# Clock_WR.net
KiCad netlist of a schematic drawn in Altium Designer
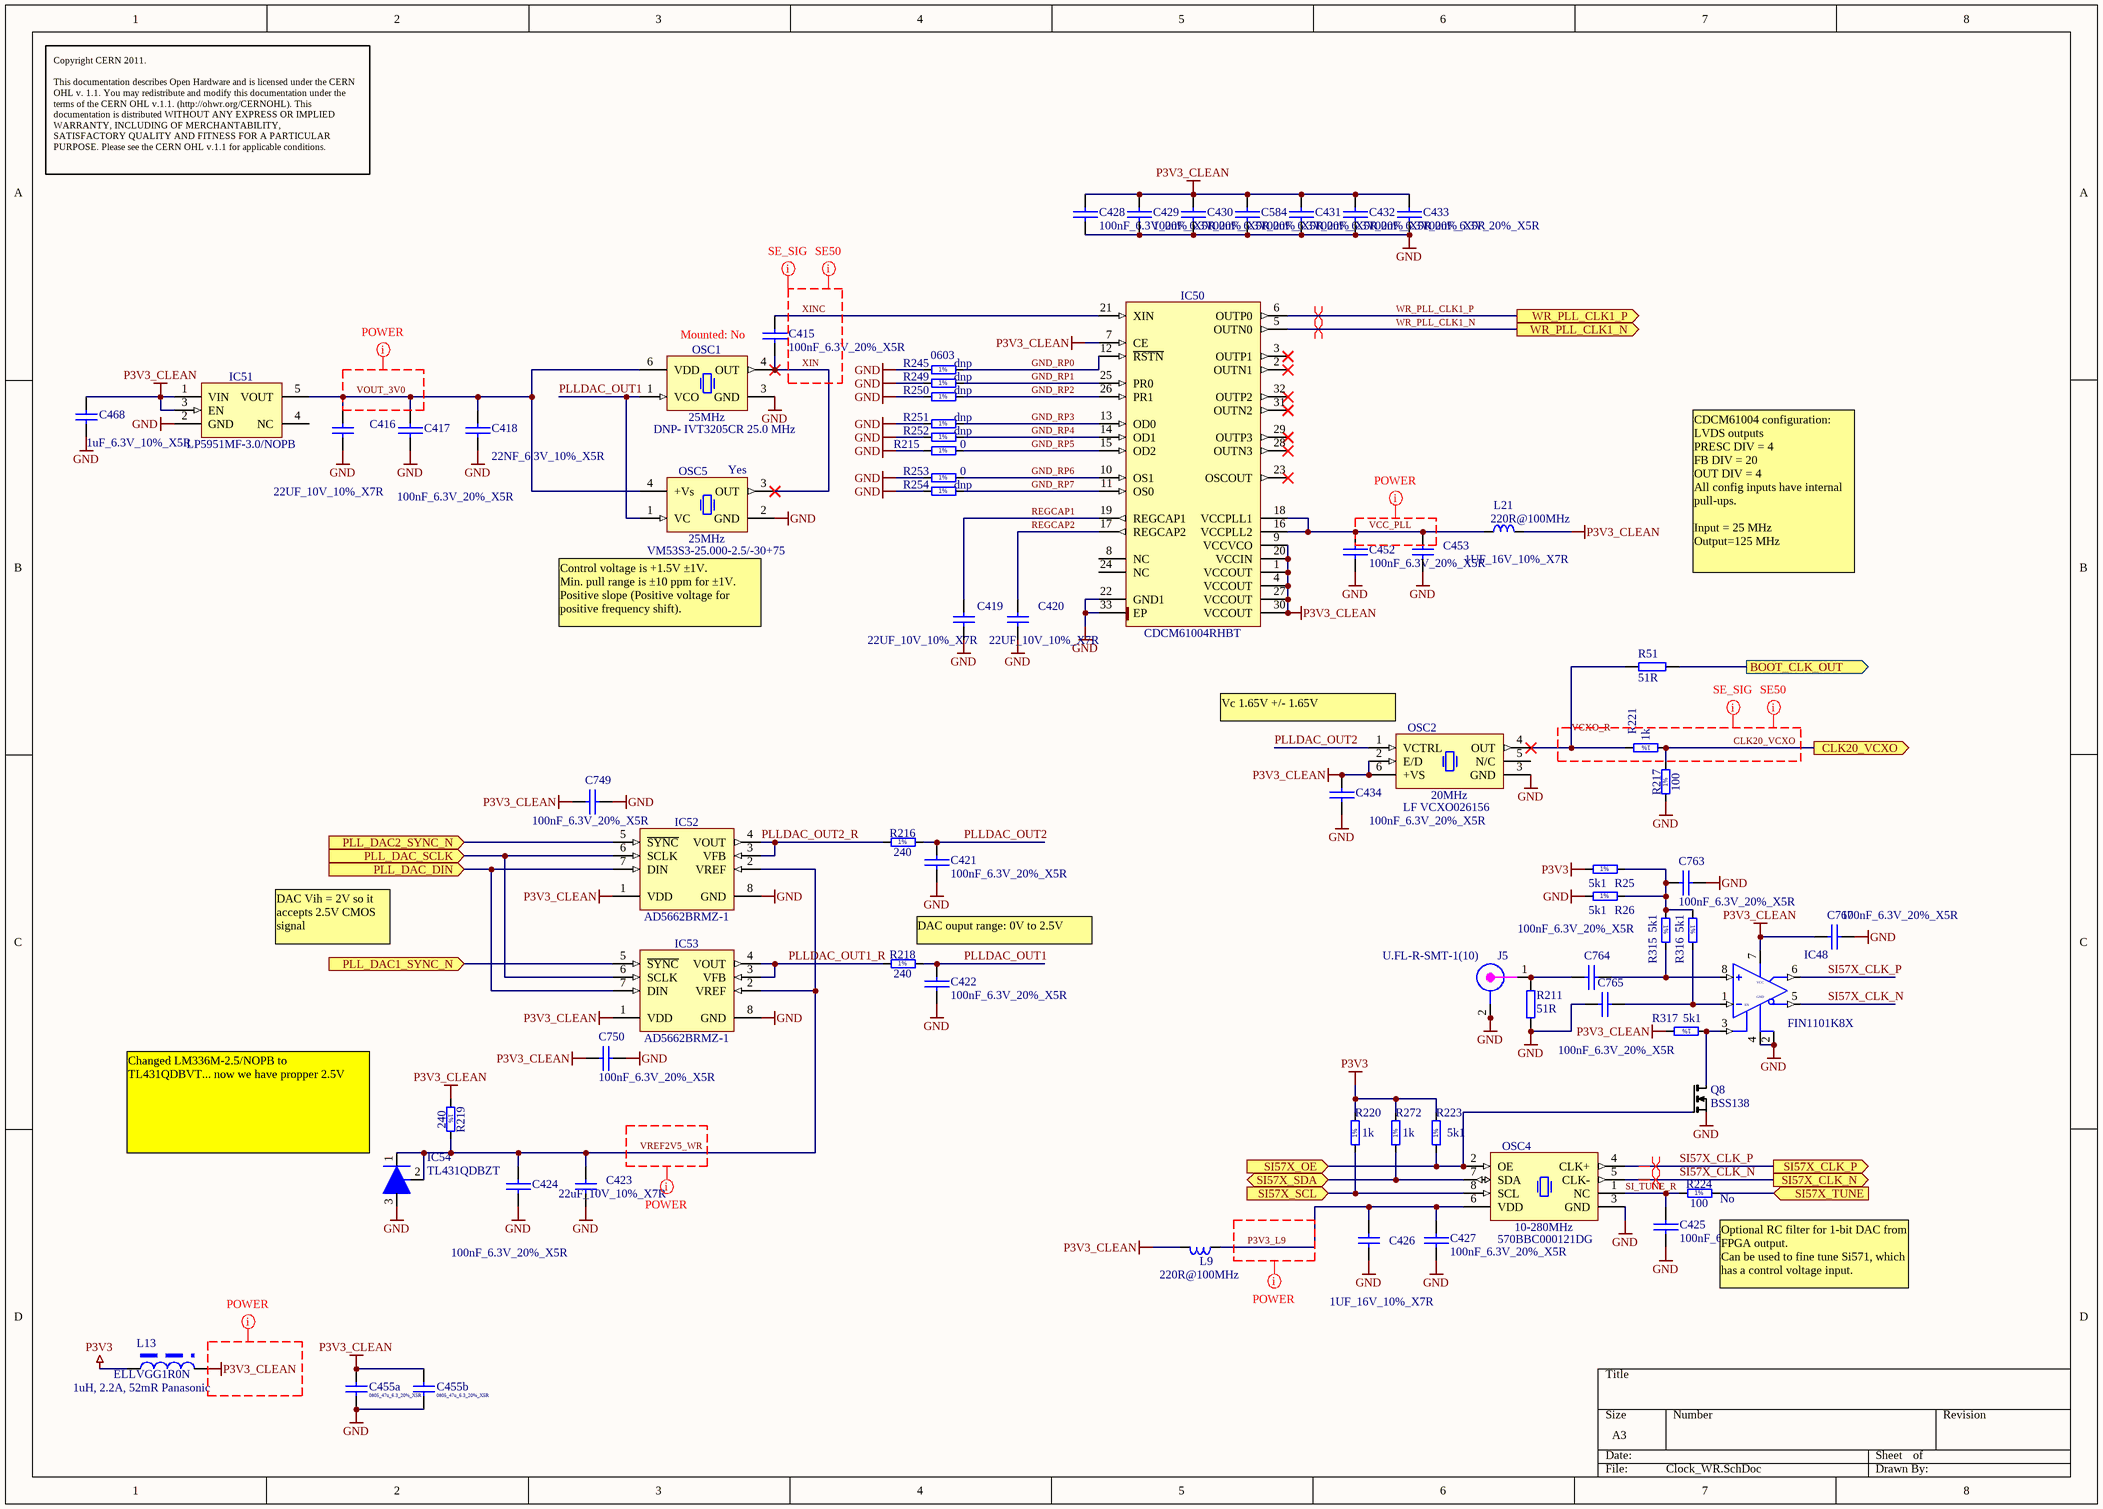
[diagram p0: Clock_WR.SchDoc]

(export (version "E")
  (design (tool "Eeschema 10.0.6"))
  (components
    (comp (ref "C415")
      (value "100nF_6.3V_20%_X5R")
      (footprint "0201C")
      (description "Capacitor SMD")
      (libsource (lib "LIBRARY_SCH") (part "CAP_SMD_0201"))
    )
    (comp (ref "C416")
      (value "22UF_10V_10%_X7R")
      (footprint "CAPC1608X87N")
      (description "Non-polarised capacitor")
      (fields
        (field (name "PART NUMBER") "CC0603_1UF_16V_10%_X7R")
        (field (name "VOLTAGE") "16V")
        (field (name "AUTHOR") "CERN DEM JLC")
      )
      (libsource (lib "Capacitors") (part "Capacitor - non polarized"))
    )
    (comp (ref "C417")
      (value "100nF_6.3V_20%_X5R")
      (footprint "0201C")
      (description "Capacitor SMD")
      (libsource (lib "LIBRARY_SCH") (part "CAP_SMD_0201"))
    )
    (comp (ref "C418")
      (value "22NF_6.3V_10%_X5R")
      (footprint "0201C")
      (description "Capacitor SMD")
      (libsource (lib "LIBRARY_SCH") (part "CAP_SMD_0201"))
    )
    (comp (ref "C419")
      (value "22UF_10V_10%_X7R")
      (footprint "CAPC3216X180N")
      (description "Non-polarised capacitor")
      (fields
        (field (name "PART NUMBER") "CC1206_22UF_10V_10%_X7R")
        (field (name "VOLTAGE") "10V")
        (field (name "AUTHOR") "CERN DEM JLC")
      )
      (libsource (lib "Capacitors") (part "Capacitor - non polarized"))
    )
    (comp (ref "C420")
      (value "22UF_10V_10%_X7R")
      (footprint "CAPC3216X180N")
      (description "Non-polarised capacitor")
      (fields
        (field (name "PART NUMBER") "CC1206_22UF_10V_10%_X7R")
        (field (name "VOLTAGE") "10V")
        (field (name "AUTHOR") "CERN DEM JLC")
      )
      (libsource (lib "Capacitors") (part "Capacitor - non polarized"))
    )
    (comp (ref "C421")
      (value "100nF_6.3V_20%_X5R")
      (footprint "0201C")
      (description "Capacitor SMD")
      (libsource (lib "LIBRARY_SCH") (part "CAP_SMD_0201"))
    )
    (comp (ref "C422")
      (value "100nF_6.3V_20%_X5R")
      (footprint "0201C")
      (description "Capacitor SMD")
      (libsource (lib "LIBRARY_SCH") (part "CAP_SMD_0201"))
    )
    (comp (ref "C423")
      (value "22uF_10V_10%_X7R")
      (footprint "CAPC3216X180N")
      (description "Non-polarised capacitor")
      (fields
        (field (name "PART NUMBER") "CC1206_22UF_10V_10%_X7R")
        (field (name "VOLTAGE") "10V")
        (field (name "AUTHOR") "CERN DEM JLC")
      )
      (libsource (lib "Capacitors") (part "Capacitor - non polarized"))
    )
    (comp (ref "C424")
      (value "100nF_6.3V_20%_X5R")
      (footprint "0201C")
      (description "Capacitor SMD")
      (libsource (lib "LIBRARY_SCH") (part "CAP_SMD_0201"))
    )
    (comp (ref "C425")
      (value "100nF_6.3V_20%_X5R")
      (footprint "0201C")
      (description "Capacitor SMD")
      (libsource (lib "LIBRARY_SCH") (part "CAP_SMD_0201"))
    )
    (comp (ref "C426")
      (value "1UF_16V_10%_X7R")
      (footprint "CAPC1608X87N")
      (description "Non-polarised capacitor")
      (fields
        (field (name "PART NUMBER") "CC0603_1UF_16V_10%_X7R")
        (field (name "VOLTAGE") "16V")
        (field (name "AUTHOR") "CERN DEM JLC")
      )
      (libsource (lib "Capacitors") (part "Capacitor - non polarized"))
    )
    (comp (ref "C427")
      (value "100nF_6.3V_20%_X5R")
      (footprint "0201C")
      (description "Capacitor SMD")
      (libsource (lib "LIBRARY_SCH") (part "CAP_SMD_0201"))
    )
    (comp (ref "C428")
      (value "100nF_6.3V_20%_X5R")
      (footprint "0201C")
      (description "Capacitor SMD")
      (libsource (lib "LIBRARY_SCH") (part "CAP_SMD_0201"))
    )
    (comp (ref "C429")
      (value "100nF_6.3V_20%_X5R")
      (footprint "0201C")
      (description "Capacitor SMD")
      (libsource (lib "LIBRARY_SCH") (part "CAP_SMD_0201"))
    )
    (comp (ref "C430")
      (value "100nF_6.3V_20%_X5R")
      (footprint "0201C")
      (description "Capacitor SMD")
      (libsource (lib "LIBRARY_SCH") (part "CAP_SMD_0201"))
    )
    (comp (ref "C431")
      (value "100nF_6.3V_20%_X5R")
      (footprint "0201C")
      (description "Capacitor SMD")
      (libsource (lib "LIBRARY_SCH") (part "CAP_SMD_0201"))
    )
    (comp (ref "C432")
      (value "100nF_6.3V_20%_X5R")
      (footprint "0201C")
      (description "Capacitor SMD")
      (libsource (lib "LIBRARY_SCH") (part "CAP_SMD_0201"))
    )
    (comp (ref "C433")
      (value "100nF_6.3V_20%_X5R")
      (footprint "0201C")
      (description "Capacitor SMD")
      (libsource (lib "LIBRARY_SCH") (part "CAP_SMD_0201"))
    )
    (comp (ref "C434")
      (value "100nF_6.3V_20%_X5R")
      (footprint "0201C")
      (description "Capacitor SMD")
      (libsource (lib "LIBRARY_SCH") (part "CAP_SMD_0201"))
    )
    (comp (ref "C452")
      (value "100nF_6.3V_20%_X5R")
      (footprint "0201C")
      (description "Capacitor SMD")
      (libsource (lib "LIBRARY_SCH") (part "CAP_SMD_0201"))
    )
    (comp (ref "C453")
      (value "1UF_16V_10%_X7R")
      (footprint "CAPC1608X87N")
      (description "Non-polarised capacitor")
      (fields
        (field (name "PART NUMBER") "CC0603_1UF_16V_10%_X7R")
        (field (name "VOLTAGE") "16V")
        (field (name "AUTHOR") "CERN DEM JLC")
      )
      (libsource (lib "Capacitors") (part "Capacitor - non polarized"))
    )
    (comp (ref "C455a")
      (value "0805_47u_6.3_20%_X5R")
      (footprint "CAPC2012X140N")
      (fields (field (name "PART NUMBER") "Ceramic_0805"))
      (libsource (lib "Capacitors") (part "Capacitor"))
    )
    (comp (ref "C455b")
      (value "0805_47u_6.3_20%_X5R")
      (footprint "CAPC2012X140N")
      (fields (field (name "PART NUMBER") "Ceramic_0805"))
      (libsource (lib "Capacitors") (part "Capacitor"))
    )
    (comp (ref "C468")
      (value "1uF_6.3V_10%_X5R")
      (footprint "CAPC1608X87N")
      (description "Non-polarised capacitor")
      (fields
        (field (name "PART NUMBER") "CC0603_1UF_16V_10%_X7R")
        (field (name "VOLTAGE") "16V")
        (field (name "AUTHOR") "CERN DEM JLC")
      )
      (libsource (lib "Capacitors") (part "Capacitor - non polarized"))
    )
    (comp (ref "C584")
      (value "100nF_6.3V_20%_X5R")
      (footprint "0201C")
      (description "Capacitor SMD")
      (libsource (lib "LIBRARY_SCH") (part "CAP_SMD_0201"))
    )
    (comp (ref "C749")
      (value "100nF_6.3V_20%_X5R")
      (footprint "0201C")
      (description "Capacitor SMD")
      (libsource (lib "LIBRARY_SCH") (part "CAP_SMD_0201"))
    )
    (comp (ref "C750")
      (value "100nF_6.3V_20%_X5R")
      (footprint "0201C")
      (description "Capacitor SMD")
      (libsource (lib "LIBRARY_SCH") (part "CAP_SMD_0201"))
    )
    (comp (ref "C763")
      (value "100nF_6.3V_20%_X5R")
      (footprint "0201C")
      (description "Capacitor SMD")
      (libsource (lib "LIBRARY_SCH") (part "CAP_SMD_0201"))
    )
    (comp (ref "C764")
      (value "100nF_6.3V_20%_X5R")
      (footprint "0201C")
      (description "Capacitor SMD")
      (libsource (lib "LIBRARY_SCH") (part "CAP_SMD_0201"))
    )
    (comp (ref "C765")
      (value "100nF_6.3V_20%_X5R")
      (footprint "0201C")
      (description "Capacitor SMD")
      (libsource (lib "LIBRARY_SCH") (part "CAP_SMD_0201"))
    )
    (comp (ref "C767")
      (value "100nF_6.3V_20%_X5R")
      (footprint "0201C")
      (description "Capacitor SMD")
      (libsource (lib "LIBRARY_SCH") (part "CAP_SMD_0201"))
    )
    (comp (ref "IC48")
      (value "FIN1101K8X")
      (footprint "US8")
      (description "LVDS TO LVDS repeater3.3V")
      (libsource (lib "AMC_FMC_Carrier") (part "IFC_FIN1101K8X"))
    )
    (comp (ref "IC50")
      (value "CDCM61004RHBT")
      (footprint "QFN50P500X500X100-33N-S355")
      (description "Four Output, Integrated VCO, Low-Jitter Clock Generator")
      (fields (field (name "MANUFACTURER") "TEXAS INSTRUMENTS") (field (name "AUTHOR") "CERN DEM JLC"))
      (libsource (lib "ICs And Semiconductors") (part "CDCM61004RHB"))
    )
    (comp (ref "IC51")
      (value "LP5951MF-3.0/NOPB")
      (footprint "SOT95P284X122-5N")
      (description "150mA Micropower Low-Dropout CMOS Voltage Regulator")
      (fields (field (name "MANUFACTURER") "NATIONAL SEMICONDUCTOR") (field (name "AUTHOR") "CERN DEM JLC"))
      (libsource (lib "ICs And Semiconductors") (part "LP5951"))
    )
    (comp (ref "IC52")
      (value "AD5662BRMZ-1")
      (footprint "SOP65P490X110-8N")
      (description "2.7V to 5.5V, 250uA, Rail-to-Rail Output 16-Bit nanoDAC")
      (fields (field (name "MANUFACTURER") "ANALOG DEVICES") (field (name "AUTHOR") "CERN DEM JLC"))
      (libsource (lib "ICs And Semiconductors") (part "AD5662"))
    )
    (comp (ref "IC53")
      (value "AD5662BRMZ-1")
      (footprint "SOP65P490X110-8N")
      (description "2.7V to 5.5V, 250uA, Rail-to-Rail Output 16-Bit nanoDAC")
      (fields (field (name "MANUFACTURER") "ANALOG DEVICES") (field (name "AUTHOR") "CERN DEM JLC"))
      (libsource (lib "ICs And Semiconductors") (part "AD5662"))
    )
    (comp (ref "IC54")
      (value "TL431QDBZT")
      (footprint "SOT-23")
      (description "2.5V ADJ Voltage reference")
      (libsource (lib "LIBRARY_SCH") (part "REF_TL431_SOT23"))
    )
    (comp (ref "J5")
      (value "U.FL-R-SMT-1(10)")
      (footprint "CON_UFL_HIROSE_RECEPTACLE")
      (description "UFL")
      (libsource (lib "LIBRARY_SCH") (part "CON_UFL_SMD"))
    )
    (comp (ref "L9")
      (value "220R@100MHz")
      (footprint "INDC2012X105N")
      (description "Inductor")
      (fields
        (field (name "PART NUMBER") "IND0805_MURATA_BLM21PG221SN1D")
        (field (name "POWER") "2A")
        (field (name "AUTHOR") "CERN DEM JLC")
      )
      (libsource (lib "Inductors & Transformers") (part "Inductor"))
    )
    (comp (ref "L13")
      (value "ELLVGG1R0N")
      (footprint "L_ELLVGG2R2N")
      (description "2.2uH, 1.4A, 92mR Panasonic")
      (fields (field (name "ALTIUM_UNNAMED_1") "1uH, 2.2A, 52mR Panasonic"))
      (libsource (lib "LIBRARY_SCH") (part "L_CHOKE_ELLVGG"))
    )
    (comp (ref "L21")
      (value "220R@100MHz")
      (footprint "INDC2012X105N")
      (description "Inductor")
      (fields
        (field (name "PART NUMBER") "IND0805_MURATA_BLM21PG221SN1D")
        (field (name "POWER") "2A")
        (field (name "AUTHOR") "CERN DEM JLC")
      )
      (libsource (lib "Inductors & Transformers") (part "Inductor"))
    )
    (comp (ref "OSC1")
      (value "25MHz")
      (footprint "OSC_RAKON_IVT3200C")
      (description "Oscillator 4 pins 1=VCO 3=GND 4=OUT 6=VDC")
      (fields
        (field (name "PART NUMBER") "OSC_25MHZ_RAKON_IVT3205CR")
        (field (name "MANUFACTURER") "RAKON")
        (field (name "MANUFACTURER PART NUMBER") "DNP- IVT3205CR 25.0 MHz")
        (field (name "MOUNTED") "No")
        (field (name "AUTHOR") "CERN DEM JLC")
      )
      (libsource (lib "ICs And Semiconductors") (part "Oscillator 1VCO 3GND 4OUT 6VCC"))
    )
    (comp (ref "OSC2")
      (value "20MHz")
      (footprint "OSC_IQD_CFPV-45")
      (description "3.3V ±100ppm 15pF HCMOS Tri-State Surface Mount Voltage Controlled Oscillator VCXO (CFPV-45 Serie)")
      (fields
        (field (name "PART NUMBER") "OSC_20MHZ_IQD_LF VCXO026156")
        (field (name "MANUFACTURER") "IQD FREQUENCY PRODUCTS")
        (field (name "MANUFACTURER PART NUMBER") "LF VCXO026156")
        (field (name "AUTHOR") "CERN DEM JLC")
      )
      (libsource (lib "ICs And Semiconductors") (part "Oscillator IQD_CFPV-45"))
    )
    (comp (ref "OSC4")
      (value "10-280MHz")
      (footprint "OSC_SILICON-LAB_SI570")
      (description "Any-Rate I2C Programmable XO Oscillator Si570 Serie")
      (fields
        (field (name "PART NUMBER") "OSC_10-280MHZ_SILICON-LAB_Si570BBC000121DG")
        (field (name "MANUFACTURER") "SILICON LABS")
        (field (name "MANUFACTURER PART NUMBER") "570BBC000121DG")
        (field (name "AUTHOR") "CERN DEM JLC")
      )
      (libsource (lib "ICs And Semiconductors") (part "Oscillator SILICON-LAB_Si570"))
    )
    (comp (ref "OSC5")
      (value "25MHz")
      (footprint "OSCCC320X500X160-4N")
      (description "Oscillator 4 pins 1=VC 2=GND 3=OUT 4=+Vs")
      (fields
        (field (name "PART NUMBER") "OSC_25MHZ_MERCURY_VM53S3-25.000-2.5/-30+75")
        (field (name "MANUFACTURER") "MERCURY ELECTRONICS")
        (field (name "MANUFACTURER PART NUMBER") "VM53S3-25.000-2.5/-30+75")
        (field (name "MOUNTED") "Yes")
        (field (name "AUTHOR") "CERN DEM JLC")
      )
      (libsource (lib "ICs And Semiconductors") (part "Oscillator 1VC 2GND 3OUT 4+Vs"))
    )
    (comp (ref "Q8") (value "BSS138") (footprint "SOT-23") (libsource (lib "LIBRARY_SCH") (part "Q_BSS138")))
    (comp (ref "R25")
      (value "5k1")
      (footprint "RESC1608X55N")
      (description "Resistor - 1%")
      (fields
        (field (name "PART NUMBER") "R0603_5K1_1%_0.1W_100PPM")
        (field (name "POWER") "0.1W")
        (field (name "AUTHOR") "CERN DEM JLC")
      )
      (libsource (lib "Resistors") (part "Resistor - 1%"))
    )
    (comp (ref "R26")
      (value "5k1")
      (footprint "RESC1608X55N")
      (description "Resistor - 1%")
      (fields
        (field (name "PART NUMBER") "R0603_5K1_1%_0.1W_100PPM")
        (field (name "POWER") "0.1W")
        (field (name "AUTHOR") "CERN DEM JLC")
      )
      (libsource (lib "Resistors") (part "Resistor - 1%"))
    )
    (comp (ref "R51")
      (value "51R")
      (footprint "0402R")
      (description "SMD Resistor")
      (libsource (lib "LIBRARY_SCH") (part "RES_0402"))
    )
    (comp (ref "R211")
      (value "51R")
      (footprint "0402R")
      (description "SMD Resistor")
      (libsource (lib "LIBRARY_SCH") (part "RES_0402"))
    )
    (comp (ref "R215")
      (value "0")
      (footprint "RESC1608X55N")
      (description "Resistor - 1%")
      (fields
        (field (name "PART NUMBER") "R0603_0R_JUMPER")
        (field (name "MANUFACTURER") "GENERIC")
        (field (name "AUTHOR") "CERN DEM JLC")
      )
      (libsource (lib "Resistors") (part "Resistor - 1%"))
    )
    (comp (ref "R216")
      (value "240")
      (footprint "RESC1608X55N")
      (description "Resistor - 1%")
      (fields
        (field (name "PART NUMBER") "R0603_240R_1%_0.1W_100PPM")
        (field (name "POWER") "0.1W")
        (field (name "AUTHOR") "CERN DEM JLC")
      )
      (libsource (lib "Resistors") (part "Resistor - 1%"))
    )
    (comp (ref "R217")
      (value "100")
      (footprint "RESC1608X55N")
      (description "Resistor - 1%")
      (fields
        (field (name "PART NUMBER") "R0603_100R_1%_0.1W_100PPM")
        (field (name "POWER") "0.1W")
        (field (name "AUTHOR") "CERN DEM JLC")
      )
      (libsource (lib "Resistors") (part "Resistor - 1%"))
    )
    (comp (ref "R218")
      (value "240")
      (footprint "RESC1608X55N")
      (description "Resistor - 1%")
      (fields
        (field (name "PART NUMBER") "R0603_240R_1%_0.1W_100PPM")
        (field (name "POWER") "0.1W")
        (field (name "AUTHOR") "CERN DEM JLC")
      )
      (libsource (lib "Resistors") (part "Resistor - 1%"))
    )
    (comp (ref "R219")
      (value "240")
      (footprint "RESC1608X55N")
      (description "Resistor - 1%")
      (fields
        (field (name "PART NUMBER") "R0603_240R_1%_0.1W_100PPM")
        (field (name "POWER") "0.1W")
        (field (name "AUTHOR") "CERN DEM JLC")
      )
      (libsource (lib "Resistors") (part "Resistor - 1%"))
    )
    (comp (ref "R220")
      (value "1k")
      (footprint "RESC1608X55N")
      (description "Resistor - 1%")
      (fields
        (field (name "PART NUMBER") "R0603_1K_1%_0.1W_100PPM")
        (field (name "POWER") "0.1W")
        (field (name "AUTHOR") "CERN DEM JLC")
      )
      (libsource (lib "Resistors") (part "Resistor - 1%"))
    )
    (comp (ref "R221")
      (value "1k")
      (footprint "RESC1608X55N")
      (description "Resistor - 1%")
      (fields
        (field (name "PART NUMBER") "R0603_1K_1%_0.1W_100PPM")
        (field (name "POWER") "0.1W")
        (field (name "AUTHOR") "CERN DEM JLC")
      )
      (libsource (lib "Resistors") (part "Resistor - 1%"))
    )
    (comp (ref "R223")
      (value "5k1")
      (footprint "RESC1608X55N")
      (description "Resistor - 1%")
      (fields
        (field (name "PART NUMBER") "R0603_5K1_1%_0.1W_100PPM")
        (field (name "POWER") "0.1W")
        (field (name "AUTHOR") "CERN DEM JLC")
      )
      (libsource (lib "Resistors") (part "Resistor - 1%"))
    )
    (comp (ref "R224")
      (value "100")
      (footprint "RESC1608X55N")
      (description "Resistor - 1%")
      (fields
        (field (name "PART NUMBER") "R0603_100R_1%_0.1W_100PPM")
        (field (name "POWER") "0.1W")
        (field (name "MOUNTED") "No")
        (field (name "AUTHOR") "CERN DEM JLC")
      )
      (libsource (lib "Resistors") (part "Resistor - 1%"))
    )
    (comp (ref "R245")
      (value "dnp")
      (footprint "RESC1608X55N")
      (description "Resistor - 1%")
      (fields
        (field (name "PART NUMBER") "R0603_0R_JUMPER")
        (field (name "MANUFACTURER") "GENERIC")
        (field (name "CASE") "0603")
        (field (name "AUTHOR") "CERN DEM JLC")
      )
      (libsource (lib "Resistors") (part "Resistor - 1%"))
    )
    (comp (ref "R249")
      (value "dnp")
      (footprint "RESC1608X55N")
      (description "Resistor - 1%")
      (fields
        (field (name "PART NUMBER") "R0603_0R_JUMPER")
        (field (name "MANUFACTURER") "GENERIC")
        (field (name "AUTHOR") "CERN DEM JLC")
      )
      (libsource (lib "Resistors") (part "Resistor - 1%"))
    )
    (comp (ref "R250")
      (value "dnp")
      (footprint "RESC1608X55N")
      (description "Resistor - 1%")
      (fields
        (field (name "PART NUMBER") "R0603_0R_JUMPER")
        (field (name "MANUFACTURER") "GENERIC")
        (field (name "AUTHOR") "CERN DEM JLC")
      )
      (libsource (lib "Resistors") (part "Resistor - 1%"))
    )
    (comp (ref "R251")
      (value "dnp")
      (footprint "RESC1608X55N")
      (description "Resistor - 1%")
      (fields
        (field (name "PART NUMBER") "R0603_0R_JUMPER")
        (field (name "MANUFACTURER") "GENERIC")
        (field (name "AUTHOR") "CERN DEM JLC")
      )
      (libsource (lib "Resistors") (part "Resistor - 1%"))
    )
    (comp (ref "R252")
      (value "dnp")
      (footprint "RESC1608X55N")
      (description "Resistor - 1%")
      (fields
        (field (name "PART NUMBER") "R0603_0R_JUMPER")
        (field (name "MANUFACTURER") "GENERIC")
        (field (name "AUTHOR") "CERN DEM JLC")
      )
      (libsource (lib "Resistors") (part "Resistor - 1%"))
    )
    (comp (ref "R253")
      (value "0")
      (footprint "RESC1608X55N")
      (description "Resistor - 1%")
      (fields
        (field (name "PART NUMBER") "R0603_0R_JUMPER")
        (field (name "MANUFACTURER") "GENERIC")
        (field (name "AUTHOR") "CERN DEM JLC")
      )
      (libsource (lib "Resistors") (part "Resistor - 1%"))
    )
    (comp (ref "R254")
      (value "dnp")
      (footprint "RESC1608X55N")
      (description "Resistor - 1%")
      (fields
        (field (name "PART NUMBER") "R0603_0R_JUMPER")
        (field (name "MANUFACTURER") "GENERIC")
        (field (name "AUTHOR") "CERN DEM JLC")
      )
      (libsource (lib "Resistors") (part "Resistor - 1%"))
    )
    (comp (ref "R272")
      (value "1k")
      (footprint "RESC1608X55N")
      (description "Resistor - 1%")
      (fields
        (field (name "PART NUMBER") "R0603_1K_1%_0.1W_100PPM")
        (field (name "POWER") "0.1W")
        (field (name "AUTHOR") "CERN DEM JLC")
      )
      (libsource (lib "Resistors") (part "Resistor - 1%"))
    )
    (comp (ref "R315")
      (value "5k1")
      (footprint "RESC1608X55N")
      (description "Resistor - 1%")
      (fields
        (field (name "PART NUMBER") "R0603_5K1_1%_0.1W_100PPM")
        (field (name "POWER") "0.1W")
        (field (name "AUTHOR") "CERN DEM JLC")
      )
      (libsource (lib "Resistors") (part "Resistor - 1%"))
    )
    (comp (ref "R316")
      (value "5k1")
      (footprint "RESC1608X55N")
      (description "Resistor - 1%")
      (fields
        (field (name "PART NUMBER") "R0603_5K1_1%_0.1W_100PPM")
        (field (name "POWER") "0.1W")
        (field (name "AUTHOR") "CERN DEM JLC")
      )
      (libsource (lib "Resistors") (part "Resistor - 1%"))
    )
    (comp (ref "R317")
      (value "5k1")
      (footprint "RESC1608X55N")
      (description "Resistor - 1%")
      (fields
        (field (name "PART NUMBER") "R0603_5K1_1%_0.1W_100PPM")
        (field (name "POWER") "0.1W")
        (field (name "AUTHOR") "CERN DEM JLC")
      )
      (libsource (lib "Resistors") (part "Resistor - 1%"))
    )
  )
  (nets
    (net (code "1") (name "/BOOT_CLK_OUT") (class "Default")
      (node (ref "R51") (pin "2") (pinfunction "2_2") (pintype "passive"))
    )
    (net (code "2") (name "/CLK20_VCXO") (class "Default")
      (node (ref "R217") (pin "2") (pinfunction "2_2") (pintype "passive"))
      (node (ref "R221") (pin "1") (pinfunction "1_1") (pintype "passive"))
    )
    (net (code "3") (name "/GND_RP0") (class "Default")
      (node (ref "IC50") (pin "12") (pinfunction "~{RSTN}_12") (pintype "input"))
      (node (ref "R245") (pin "2") (pinfunction "2_2") (pintype "passive"))
    )
    (net (code "4") (name "/GND_RP1") (class "Default")
      (node (ref "IC50") (pin "25") (pinfunction "PR0_25") (pintype "input"))
      (node (ref "R249") (pin "2") (pinfunction "2_2") (pintype "passive"))
    )
    (net (code "5") (name "/GND_RP2") (class "Default")
      (node (ref "IC50") (pin "26") (pinfunction "PR1_26") (pintype "input"))
      (node (ref "R250") (pin "2") (pinfunction "2_2") (pintype "passive"))
    )
    (net (code "6") (name "/GND_RP3") (class "Default")
      (node (ref "IC50") (pin "13") (pinfunction "OD0_13") (pintype "input"))
      (node (ref "R251") (pin "2") (pinfunction "2_2") (pintype "passive"))
    )
    (net (code "7") (name "/GND_RP4") (class "Default")
      (node (ref "IC50") (pin "14") (pinfunction "OD1_14") (pintype "input"))
      (node (ref "R252") (pin "2") (pinfunction "2_2") (pintype "passive"))
    )
    (net (code "8") (name "/GND_RP5") (class "Default")
      (node (ref "IC50") (pin "15") (pinfunction "OD2_15") (pintype "input"))
      (node (ref "R215") (pin "2") (pinfunction "2_2") (pintype "passive"))
    )
    (net (code "9") (name "/GND_RP6") (class "Default")
      (node (ref "IC50") (pin "10") (pinfunction "OS1_10") (pintype "input"))
      (node (ref "R253") (pin "2") (pinfunction "2_2") (pintype "passive"))
    )
    (net (code "10") (name "/GND_RP7") (class "Default")
      (node (ref "IC50") (pin "11") (pinfunction "OS0_11") (pintype "input"))
      (node (ref "R254") (pin "2") (pinfunction "2_2") (pintype "passive"))
    )
    (net (code "11") (name "/P3V3_L9") (class "Default")
      (node (ref "C426") (pin "2") (pinfunction "2_2") (pintype "passive"))
      (node (ref "C427") (pin "1") (pinfunction "1_1") (pintype "passive"))
      (node (ref "L9") (pin "1") (pinfunction "1_1") (pintype "passive"))
      (node (ref "OSC4") (pin "6") (pinfunction "VDD_6") (pintype "power_in"))
    )
    (net (code "12") (name "/PLLDAC_OUT1") (class "Default")
      (node (ref "C422") (pin "1") (pinfunction "1_1") (pintype "passive"))
      (node (ref "OSC1") (pin "1") (pinfunction "VCO_1") (pintype "input"))
      (node (ref "OSC5") (pin "1") (pinfunction "VC_1") (pintype "input"))
      (node (ref "R218") (pin "2") (pinfunction "2_2") (pintype "passive"))
    )
    (net (code "13") (name "/PLLDAC_OUT1_R") (class "Default")
      (node (ref "IC53") (pin "3") (pinfunction "VFB_3") (pintype "input"))
      (node (ref "IC53") (pin "4") (pinfunction "VOUT_4") (pintype "output"))
      (node (ref "R218") (pin "1") (pinfunction "1_1") (pintype "passive"))
    )
    (net (code "14") (name "/PLLDAC_OUT2") (class "Default")
      (node (ref "C421") (pin "1") (pinfunction "1_1") (pintype "passive"))
      (node (ref "OSC2") (pin "1") (pinfunction "VCTRL_1") (pintype "input"))
      (node (ref "R216") (pin "2") (pinfunction "2_2") (pintype "passive"))
    )
    (net (code "15") (name "/PLLDAC_OUT2_R") (class "Default")
      (node (ref "IC52") (pin "3") (pinfunction "VFB_3") (pintype "input"))
      (node (ref "IC52") (pin "4") (pinfunction "VOUT_4") (pintype "output"))
      (node (ref "R216") (pin "1") (pinfunction "1_1") (pintype "passive"))
    )
    (net (code "16") (name "/PLL_DAC1_SYNC_N") (class "Default")
      (node (ref "IC53") (pin "5") (pinfunction "~{SYNC}_5") (pintype "input"))
    )
    (net (code "17") (name "/PLL_DAC2_SYNC_N") (class "Default")
      (node (ref "IC52") (pin "5") (pinfunction "~{SYNC}_5") (pintype "input"))
    )
    (net (code "18") (name "/PLL_DAC_DIN") (class "Default")
      (node (ref "IC52") (pin "7") (pinfunction "DIN_7") (pintype "input"))
      (node (ref "IC53") (pin "7") (pinfunction "DIN_7") (pintype "input"))
    )
    (net (code "19") (name "/PLL_DAC_SCLK") (class "Default")
      (node (ref "IC52") (pin "6") (pinfunction "SCLK_6") (pintype "input"))
      (node (ref "IC53") (pin "6") (pinfunction "SCLK_6") (pintype "input"))
    )
    (net (code "20") (name "/REGCAP1") (class "Default")
      (node (ref "C419") (pin "2") (pinfunction "2_2") (pintype "passive"))
      (node (ref "IC50") (pin "19") (pinfunction "REGCAP1_19") (pintype "output"))
    )
    (net (code "21") (name "/REGCAP2") (class "Default")
      (node (ref "C420") (pin "2") (pinfunction "2_2") (pintype "passive"))
      (node (ref "IC50") (pin "17") (pinfunction "REGCAP2_17") (pintype "output"))
    )
    (net (code "22") (name "/SI57X_CLK_N") (class "Default")
      (node (ref "IC48") (pin "5") (pinfunction "~{Q}_5") (pintype "output"))
      (node (ref "OSC4") (pin "5") (pinfunction "CLK-_5") (pintype "output"))
    )
    (net (code "23") (name "/SI57X_CLK_P") (class "Default")
      (node (ref "IC48") (pin "6") (pinfunction "Q_6") (pintype "output"))
      (node (ref "OSC4") (pin "4") (pinfunction "CLK+_4") (pintype "output"))
    )
    (net (code "24") (name "/SI57X_OE") (class "Default")
      (node (ref "OSC4") (pin "2") (pinfunction "OE_2") (pintype "input"))
      (node (ref "Q8") (pin "1") (pinfunction "G_1") (pintype "input"))
      (node (ref "R223") (pin "1") (pinfunction "1_1") (pintype "passive"))
    )
    (net (code "25") (name "/SI57X_SCL") (class "Default")
      (node (ref "OSC4") (pin "8") (pinfunction "SCL_8") (pintype "input"))
      (node (ref "R220") (pin "1") (pinfunction "1_1") (pintype "passive"))
    )
    (net (code "26") (name "/SI57X_SDA") (class "Default")
      (node (ref "OSC4") (pin "7") (pinfunction "SDA_7") (pintype "bidirectional"))
      (node (ref "R272") (pin "1") (pinfunction "1_1") (pintype "passive"))
    )
    (net (code "27") (name "/SI57X_TUNE") (class "Default")
      (node (ref "R224") (pin "2") (pinfunction "2_2") (pintype "passive"))
    )
    (net (code "28") (name "/SI_TUNE_R") (class "Default")
      (node (ref "C425") (pin "1") (pinfunction "1_1") (pintype "passive"))
      (node (ref "OSC4") (pin "1") (pinfunction "NC_1") (pintype "passive"))
      (node (ref "R224") (pin "1") (pinfunction "1_1") (pintype "passive"))
    )
    (net (code "29") (name "/VCC_PLL") (class "Default")
      (node (ref "C452") (pin "1") (pinfunction "1_1") (pintype "passive"))
      (node (ref "C453") (pin "2") (pinfunction "2_2") (pintype "passive"))
      (node (ref "IC50") (pin "16") (pinfunction "VCCPLL2_16") (pintype "power_in"))
      (node (ref "IC50") (pin "18") (pinfunction "VCCPLL1_18") (pintype "power_in"))
      (node (ref "L21") (pin "1") (pinfunction "1_1") (pintype "passive"))
    )
    (net (code "30") (name "/VCXO_R") (class "Default")
      (node (ref "OSC2") (pin "4") (pinfunction "OUT_4") (pintype "output"))
      (node (ref "R221") (pin "2") (pinfunction "2_2") (pintype "passive"))
      (node (ref "R51") (pin "1") (pinfunction "1_1") (pintype "passive"))
    )
    (net (code "31") (name "/VOUT_3V0") (class "Default")
      (node (ref "C416") (pin "2") (pinfunction "2_2") (pintype "passive"))
      (node (ref "C417") (pin "1") (pinfunction "1_1") (pintype "passive"))
      (node (ref "C418") (pin "2") (pinfunction "2_2") (pintype "passive"))
      (node (ref "IC51") (pin "5") (pinfunction "VOUT_5") (pintype "power_in"))
      (node (ref "OSC1") (pin "6") (pinfunction "VDD_6") (pintype "power_in"))
      (node (ref "OSC5") (pin "4") (pinfunction "+Vs_4") (pintype "power_in"))
    )
    (net (code "32") (name "/VREF2V5_WR") (class "Default")
      (node (ref "C423") (pin "2") (pinfunction "2_2") (pintype "passive"))
      (node (ref "C424") (pin "1") (pinfunction "1_1") (pintype "passive"))
      (node (ref "IC52") (pin "2") (pinfunction "VREF_2") (pintype "input"))
      (node (ref "IC53") (pin "2") (pinfunction "VREF_2") (pintype "input"))
      (node (ref "IC54") (pin "1") (pinfunction "I/O_1") (pintype "passive"))
      (node (ref "IC54") (pin "2") (pinfunction "REF_2") (pintype "passive"))
      (node (ref "R219") (pin "2") (pinfunction "2_2") (pintype "passive"))
    )
    (net (code "33") (name "/WR_PLL_CLK1_N") (class "Default")
      (node (ref "IC50") (pin "5") (pinfunction "OUTN0_5") (pintype "output"))
    )
    (net (code "34") (name "/WR_PLL_CLK1_P") (class "Default")
      (node (ref "IC50") (pin "6") (pinfunction "OUTP0_6") (pintype "output"))
    )
    (net (code "35") (name "/XIN") (class "Default")
      (node (ref "C415") (pin "1") (pinfunction "1_1") (pintype "passive"))
      (node (ref "OSC1") (pin "4") (pinfunction "OUT_4") (pintype "output"))
      (node (ref "OSC5") (pin "3") (pinfunction "OUT_3") (pintype "output"))
    )
    (net (code "36") (name "/XINC") (class "Default")
      (node (ref "C415") (pin "2") (pinfunction "2_2") (pintype "passive"))
      (node (ref "IC50") (pin "21") (pinfunction "XIN_21") (pintype "input"))
    )
    (net (code "37") (name "GND") (class "Default")
      (node (ref "C416") (pin "1") (pinfunction "1_1") (pintype "passive"))
      (node (ref "C417") (pin "2") (pinfunction "2_2") (pintype "passive"))
      (node (ref "C418") (pin "1") (pinfunction "1_1") (pintype "passive"))
      (node (ref "C419") (pin "1") (pinfunction "1_1") (pintype "passive"))
      (node (ref "C420") (pin "1") (pinfunction "1_1") (pintype "passive"))
      (node (ref "C421") (pin "2") (pinfunction "2_2") (pintype "passive"))
      (node (ref "C422") (pin "2") (pinfunction "2_2") (pintype "passive"))
      (node (ref "C423") (pin "1") (pinfunction "1_1") (pintype "passive"))
      (node (ref "C424") (pin "2") (pinfunction "2_2") (pintype "passive"))
      (node (ref "C425") (pin "2") (pinfunction "2_2") (pintype "passive"))
      (node (ref "C426") (pin "1") (pinfunction "1_1") (pintype "passive"))
      (node (ref "C427") (pin "2") (pinfunction "2_2") (pintype "passive"))
      (node (ref "C428") (pin "1") (pinfunction "1_1") (pintype "passive"))
      (node (ref "C429") (pin "2") (pinfunction "2_2") (pintype "passive"))
      (node (ref "C430") (pin "2") (pinfunction "2_2") (pintype "passive"))
      (node (ref "C431") (pin "2") (pinfunction "2_2") (pintype "passive"))
      (node (ref "C432") (pin "2") (pinfunction "2_2") (pintype "passive"))
      (node (ref "C433") (pin "2") (pinfunction "2_2") (pintype "passive"))
      (node (ref "C434") (pin "2") (pinfunction "2_2") (pintype "passive"))
      (node (ref "C452") (pin "2") (pinfunction "2_2") (pintype "passive"))
      (node (ref "C453") (pin "1") (pinfunction "1_1") (pintype "passive"))
      (node (ref "C455a") (pin "1") (pinfunction "1_1") (pintype "passive"))
      (node (ref "C455b") (pin "1") (pinfunction "1_1") (pintype "passive"))
      (node (ref "C468") (pin "1") (pinfunction "1_1") (pintype "passive"))
      (node (ref "C584") (pin "2") (pinfunction "2_2") (pintype "passive"))
      (node (ref "C749") (pin "2") (pinfunction "2_2") (pintype "passive"))
      (node (ref "C750") (pin "2") (pinfunction "2_2") (pintype "passive"))
      (node (ref "C763") (pin "2") (pinfunction "2_2") (pintype "passive"))
      (node (ref "C765") (pin "1") (pinfunction "1_1") (pintype "passive"))
      (node (ref "C767") (pin "2") (pinfunction "2_2") (pintype "passive"))
      (node (ref "IC48") (pin "2") (pinfunction "GND_2") (pintype "power_in"))
      (node (ref "IC48") (pin "4") (pinfunction "GND_4") (pintype "power_in"))
      (node (ref "IC50") (pin "22") (pinfunction "GND1_22") (pintype "power_in"))
      (node (ref "IC50") (pin "33") (pinfunction "EP_33") (pintype "power_in"))
      (node (ref "IC51") (pin "2") (pinfunction "GND_2") (pintype "power_in"))
      (node (ref "IC52") (pin "8") (pinfunction "GND_8") (pintype "power_in"))
      (node (ref "IC53") (pin "8") (pinfunction "GND_8") (pintype "power_in"))
      (node (ref "IC54") (pin "3") (pinfunction "A_3") (pintype "passive"))
      (node (ref "J5") (pin "2") (pintype "passive"))
      (node (ref "J5") (pin "2a") (pinfunction "GND_2a") (pintype "passive"))
      (node (ref "OSC1") (pin "3") (pinfunction "GND_3") (pintype "power_in"))
      (node (ref "OSC2") (pin "3") (pinfunction "GND_3") (pintype "power_in"))
      (node (ref "OSC4") (pin "3") (pinfunction "GND_3") (pintype "power_in"))
      (node (ref "OSC5") (pin "2") (pinfunction "GND_2") (pintype "power_in"))
      (node (ref "Q8") (pin "2") (pinfunction "S_2") (pintype "passive"))
      (node (ref "R211") (pin "2") (pinfunction "2_2") (pintype "passive"))
      (node (ref "R215") (pin "1") (pinfunction "1_1") (pintype "passive"))
      (node (ref "R217") (pin "1") (pinfunction "1_1") (pintype "passive"))
      (node (ref "R245") (pin "1") (pinfunction "1_1") (pintype "passive"))
      (node (ref "R249") (pin "1") (pinfunction "1_1") (pintype "passive"))
      (node (ref "R250") (pin "1") (pinfunction "1_1") (pintype "passive"))
      (node (ref "R251") (pin "1") (pinfunction "1_1") (pintype "passive"))
      (node (ref "R252") (pin "1") (pinfunction "1_1") (pintype "passive"))
      (node (ref "R253") (pin "1") (pinfunction "1_1") (pintype "passive"))
      (node (ref "R254") (pin "1") (pinfunction "1_1") (pintype "passive"))
      (node (ref "R26") (pin "1") (pinfunction "1_1") (pintype "passive"))
    )
    (net (code "38") (name "Net-(C763-Pad1)") (class "Default")
      (node (ref "C763") (pin "1") (pinfunction "1_1") (pintype "passive"))
      (node (ref "R25") (pin "2") (pinfunction "2_2") (pintype "passive"))
      (node (ref "R26") (pin "2") (pinfunction "2_2") (pintype "passive"))
      (node (ref "R315") (pin "1") (pinfunction "1_1") (pintype "passive"))
      (node (ref "R316") (pin "1") (pinfunction "1_1") (pintype "passive"))
    )
    (net (code "39") (name "Net-(C764-Pad1)") (class "Default")
      (node (ref "C764") (pin "1") (pinfunction "1_1") (pintype "passive"))
      (node (ref "J5") (pin "1") (pintype "passive"))
      (node (ref "R211") (pin "1") (pinfunction "1_1") (pintype "passive"))
    )
    (net (code "40") (name "Net-(C764-Pad2)") (class "Default")
      (node (ref "C764") (pin "2") (pinfunction "2_2") (pintype "passive"))
      (node (ref "IC48") (pin "8") (pinfunction "IN_8") (pintype "input"))
      (node (ref "R315") (pin "2") (pinfunction "2_2") (pintype "passive"))
    )
    (net (code "41") (name "Net-(C765-Pad2)") (class "Default")
      (node (ref "C765") (pin "2") (pinfunction "2_2") (pintype "passive"))
      (node (ref "IC48") (pin "1") (pinfunction "IN_1") (pintype "input"))
      (node (ref "R316") (pin "2") (pinfunction "2_2") (pintype "passive"))
    )
    (net (code "42") (name "Net-(IC48-EN)") (class "Default")
      (node (ref "IC48") (pin "3") (pinfunction "EN_3") (pintype "input"))
      (node (ref "Q8") (pin "3") (pinfunction "D_3") (pintype "passive"))
      (node (ref "R317") (pin "1") (pinfunction "1_1") (pintype "passive"))
    )
    (net (code "43") (name "P3V3") (class "Default")
      (node (ref "L13") (pin "1") (pintype "passive"))
      (node (ref "R220") (pin "2") (pinfunction "2_2") (pintype "passive"))
      (node (ref "R223") (pin "2") (pinfunction "2_2") (pintype "passive"))
      (node (ref "R25") (pin "1") (pinfunction "1_1") (pintype "passive"))
      (node (ref "R272") (pin "2") (pinfunction "2_2") (pintype "passive"))
    )
    (net (code "44") (name "P3V3_CLEAN") (class "Default")
      (node (ref "C428") (pin "2") (pinfunction "2_2") (pintype "passive"))
      (node (ref "C429") (pin "1") (pinfunction "1_1") (pintype "passive"))
      (node (ref "C430") (pin "1") (pinfunction "1_1") (pintype "passive"))
      (node (ref "C431") (pin "1") (pinfunction "1_1") (pintype "passive"))
      (node (ref "C432") (pin "1") (pinfunction "1_1") (pintype "passive"))
      (node (ref "C433") (pin "1") (pinfunction "1_1") (pintype "passive"))
      (node (ref "C434") (pin "1") (pinfunction "1_1") (pintype "passive"))
      (node (ref "C455a") (pin "2") (pinfunction "2_2") (pintype "passive"))
      (node (ref "C455b") (pin "2") (pinfunction "2_2") (pintype "passive"))
      (node (ref "C468") (pin "2") (pinfunction "2_2") (pintype "passive"))
      (node (ref "C584") (pin "1") (pinfunction "1_1") (pintype "passive"))
      (node (ref "C749") (pin "1") (pinfunction "1_1") (pintype "passive"))
      (node (ref "C750") (pin "1") (pinfunction "1_1") (pintype "passive"))
      (node (ref "C767") (pin "1") (pinfunction "1_1") (pintype "passive"))
      (node (ref "IC48") (pin "7") (pinfunction "VCC_7") (pintype "power_in"))
      (node (ref "IC50") (pin "1") (pinfunction "VCCOUT_1") (pintype "power_in"))
      (node (ref "IC50") (pin "20") (pinfunction "VCCIN_20") (pintype "power_in"))
      (node (ref "IC50") (pin "27") (pinfunction "VCCOUT_27") (pintype "power_in"))
      (node (ref "IC50") (pin "30") (pinfunction "VCCOUT_30") (pintype "power_in"))
      (node (ref "IC50") (pin "4") (pinfunction "VCCOUT_4") (pintype "power_in"))
      (node (ref "IC50") (pin "7") (pinfunction "CE_7") (pintype "input"))
      (node (ref "IC50") (pin "9") (pinfunction "VCCVCO_9") (pintype "power_in"))
      (node (ref "IC51") (pin "1") (pinfunction "VIN_1") (pintype "power_in"))
      (node (ref "IC51") (pin "3") (pinfunction "EN_3") (pintype "input"))
      (node (ref "IC52") (pin "1") (pinfunction "VDD_1") (pintype "power_in"))
      (node (ref "IC53") (pin "1") (pinfunction "VDD_1") (pintype "power_in"))
      (node (ref "L13") (pin "2") (pintype "passive"))
      (node (ref "L21") (pin "2") (pinfunction "2_2") (pintype "passive"))
      (node (ref "L9") (pin "2") (pinfunction "2_2") (pintype "passive"))
      (node (ref "OSC2") (pin "2") (pinfunction "E/D_2") (pintype "input"))
      (node (ref "OSC2") (pin "6") (pinfunction "+VS_6") (pintype "power_in"))
      (node (ref "R219") (pin "1") (pinfunction "1_1") (pintype "passive"))
      (node (ref "R317") (pin "2") (pinfunction "2_2") (pintype "passive"))
    )
    (net (code "45") (name "unconnected-(IC50-NC-Pad8)") (class "Default")
      (node (ref "IC50") (pin "8") (pinfunction "NC_8") (pintype "passive"))
    )
    (net (code "46") (name "unconnected-(IC50-NC-Pad24)") (class "Default")
      (node (ref "IC50") (pin "24") (pinfunction "NC_24") (pintype "passive"))
    )
    (net (code "47") (name "unconnected-(IC50-OSCOUT-Pad23)") (class "Default")
      (node (ref "IC50") (pin "23") (pinfunction "OSCOUT_23") (pintype "output+no_connect"))
    )
    (net (code "48") (name "unconnected-(IC50-OUTN1-Pad2)") (class "Default")
      (node (ref "IC50") (pin "2") (pinfunction "OUTN1_2") (pintype "output+no_connect"))
    )
    (net (code "49") (name "unconnected-(IC50-OUTN2-Pad31)") (class "Default")
      (node (ref "IC50") (pin "31") (pinfunction "OUTN2_31") (pintype "output+no_connect"))
    )
    (net (code "50") (name "unconnected-(IC50-OUTN3-Pad28)") (class "Default")
      (node (ref "IC50") (pin "28") (pinfunction "OUTN3_28") (pintype "output+no_connect"))
    )
    (net (code "51") (name "unconnected-(IC50-OUTP1-Pad3)") (class "Default")
      (node (ref "IC50") (pin "3") (pinfunction "OUTP1_3") (pintype "output+no_connect"))
    )
    (net (code "52") (name "unconnected-(IC50-OUTP2-Pad32)") (class "Default")
      (node (ref "IC50") (pin "32") (pinfunction "OUTP2_32") (pintype "output+no_connect"))
    )
    (net (code "53") (name "unconnected-(IC50-OUTP3-Pad29)") (class "Default")
      (node (ref "IC50") (pin "29") (pinfunction "OUTP3_29") (pintype "output+no_connect"))
    )
    (net (code "54") (name "unconnected-(IC51-NC-Pad4)") (class "Default")
      (node (ref "IC51") (pin "4") (pinfunction "NC_4") (pintype "passive"))
    )
    (net (code "55") (name "unconnected-(OSC2-N{slash}C-Pad5)") (class "Default")
      (node (ref "OSC2") (pin "5") (pinfunction "N/C_5") (pintype "passive"))
    )
  )
)
